# tictactoe.net
KiCad netlist of a schematic drawn in EAGLE
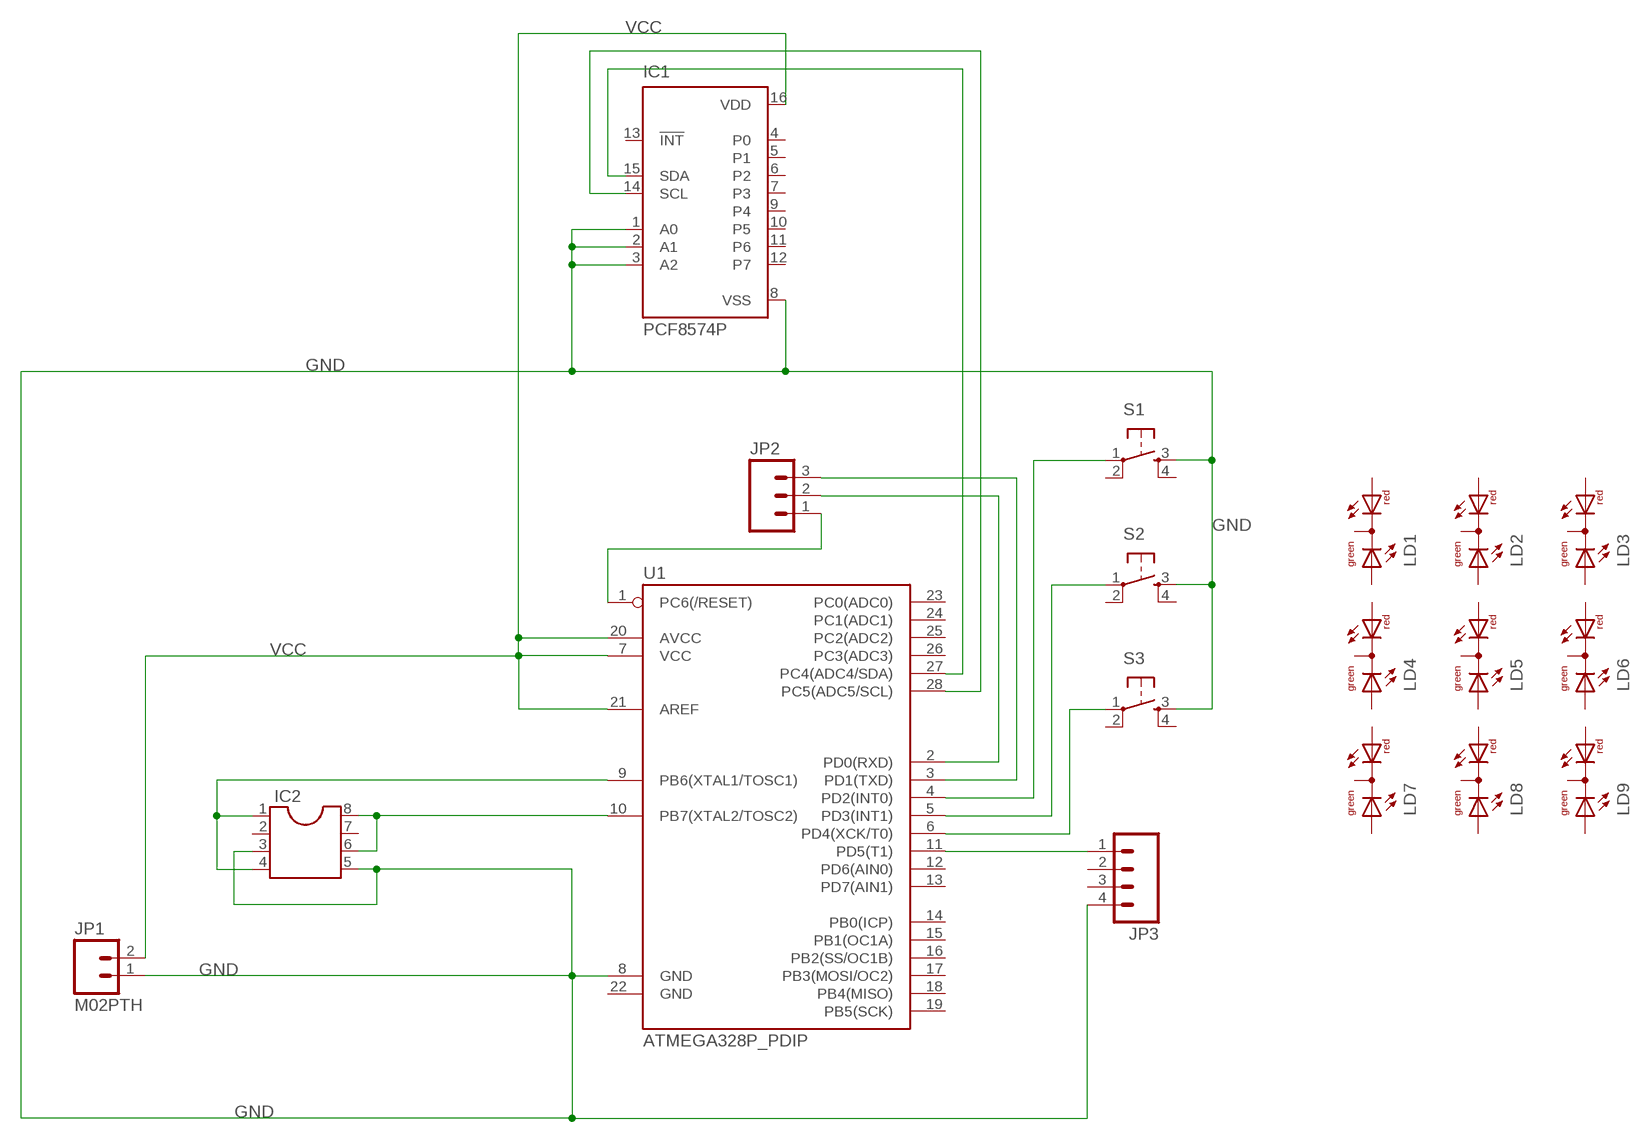
[diagram p0: schematic, sheet 1]

(export (version "E")
  (design (tool "Eeschema 10.0.6"))
  (components
    (comp (ref "IC1")
      (value "PCF8574P")
      (footprint "eagle-import:DIL16")
      (fields (field (name "MPN") "PCF8574PN"))
      (libsource (lib "eagle-import") (part "PCF8574P"))
    )
    (comp (ref "IC2")
      (value "DIL8S")
      (footprint "eagle-import:SOCKET-08")
      (libsource (lib "eagle-import") (part "DIL8S"))
    )
    (comp (ref "JP1")
      (value "M02PTH")
      (footprint "eagle-import:1X02")
      (libsource (lib "eagle-import") (part "M02PTH"))
    )
    (comp (ref "JP2")
      (value "M03PTH")
      (footprint "eagle-import:1X03")
      (libsource (lib "eagle-import") (part "M03PTH"))
    )
    (comp (ref "JP3")
      (value "M04PTH")
      (footprint "eagle-import:1X04")
      (libsource (lib "eagle-import") (part "M04PTH"))
    )
    (comp (ref "LD1")
      (value "DUOLED-RG-C")
      (footprint "eagle-import:DUOLED-C-5MM")
      (libsource (lib "eagle-import") (part "DUOLED-RG-C"))
    )
    (comp (ref "LD2")
      (value "DUOLED-RG-C")
      (footprint "eagle-import:DUOLED-C-5MM")
      (libsource (lib "eagle-import") (part "DUOLED-RG-C"))
    )
    (comp (ref "LD3")
      (value "DUOLED-RG-C")
      (footprint "eagle-import:DUOLED-C-5MM")
      (libsource (lib "eagle-import") (part "DUOLED-RG-C"))
    )
    (comp (ref "LD4")
      (value "DUOLED-RG-C")
      (footprint "eagle-import:DUOLED-C-5MM")
      (libsource (lib "eagle-import") (part "DUOLED-RG-C"))
    )
    (comp (ref "LD5")
      (value "DUOLED-RG-C")
      (footprint "eagle-import:DUOLED-C-5MM")
      (libsource (lib "eagle-import") (part "DUOLED-RG-C"))
    )
    (comp (ref "LD6")
      (value "DUOLED-RG-C")
      (footprint "eagle-import:DUOLED-C-5MM")
      (libsource (lib "eagle-import") (part "DUOLED-RG-C"))
    )
    (comp (ref "LD7")
      (value "DUOLED-RG-C")
      (footprint "eagle-import:DUOLED-C-5MM")
      (libsource (lib "eagle-import") (part "DUOLED-RG-C"))
    )
    (comp (ref "LD8")
      (value "DUOLED-RG-C")
      (footprint "eagle-import:DUOLED-C-5MM")
      (libsource (lib "eagle-import") (part "DUOLED-RG-C"))
    )
    (comp (ref "LD9")
      (value "DUOLED-RG-C")
      (footprint "eagle-import:DUOLED-C-5MM")
      (libsource (lib "eagle-import") (part "DUOLED-RG-C"))
    )
    (comp (ref "S1")
      (value "TAC_SWITCHPTH")
      (footprint "eagle-import:TACTILE-PTH")
      (libsource (lib "eagle-import") (part "TAC_SWITCHPTH"))
    )
    (comp (ref "S2")
      (value "TAC_SWITCHPTH")
      (footprint "eagle-import:TACTILE-PTH")
      (libsource (lib "eagle-import") (part "TAC_SWITCHPTH"))
    )
    (comp (ref "S3")
      (value "TAC_SWITCHPTH")
      (footprint "eagle-import:TACTILE-PTH")
      (libsource (lib "eagle-import") (part "TAC_SWITCHPTH"))
    )
    (comp (ref "U1")
      (value "ATMEGA328P_PDIP")
      (footprint "eagle-import:DIL28-3")
      (libsource (lib "eagle-import") (part "ATMEGA328P_PDIP"))
    )
  )
  (nets
    (net (code "1") (name "/GND") (class "Default")
      (node (ref "IC1") (pin "1") (pinfunction "A0_1") (pintype "input"))
      (node (ref "IC1") (pin "2") (pinfunction "A1_2") (pintype "input"))
      (node (ref "IC1") (pin "3") (pinfunction "A2_3") (pintype "input"))
      (node (ref "IC1") (pin "8") (pinfunction "VSS_8") (pintype "power_in"))
      (node (ref "IC2") (pin "3") (pinfunction "3_3") (pintype "passive"))
      (node (ref "IC2") (pin "5") (pinfunction "5_5") (pintype "passive"))
      (node (ref "JP1") (pin "1") (pinfunction "1_1") (pintype "passive"))
      (node (ref "JP3") (pin "4") (pinfunction "4_4") (pintype "passive"))
      (node (ref "S1") (pin "3") (pinfunction "3_3") (pintype "passive"))
      (node (ref "S2") (pin "3") (pinfunction "3_3") (pintype "passive"))
      (node (ref "S3") (pin "3") (pinfunction "3_3") (pintype "passive"))
      (node (ref "U1") (pin "8") (pinfunction "GND_8") (pintype "bidirectional"))
    )
    (net (code "2") (name "/VCC") (class "Default")
      (node (ref "IC1") (pin "16") (pinfunction "VDD_16") (pintype "power_in"))
      (node (ref "JP1") (pin "2") (pinfunction "2_2") (pintype "passive"))
      (node (ref "U1") (pin "20") (pinfunction "AVCC_20") (pintype "bidirectional"))
      (node (ref "U1") (pin "21") (pinfunction "AREF_21") (pintype "bidirectional"))
      (node (ref "U1") (pin "7") (pinfunction "VCC_7") (pintype "bidirectional"))
    )
    (net (code "3") (name "Net-(IC1-SCL)") (class "Default")
      (node (ref "IC1") (pin "14") (pinfunction "SCL_14") (pintype "input"))
      (node (ref "U1") (pin "28") (pinfunction "PC5(ADC5/SCL)_28") (pintype "bidirectional"))
    )
    (net (code "4") (name "Net-(IC1-SDA)") (class "Default")
      (node (ref "IC1") (pin "15") (pinfunction "SDA_15") (pintype "bidirectional"))
      (node (ref "U1") (pin "27") (pinfunction "PC4(ADC4/SDA)_27") (pintype "bidirectional"))
    )
    (net (code "5") (name "Net-(U1-PB6(XTAL1{slash}TOSC1))") (class "Default")
      (node (ref "IC2") (pin "1") (pinfunction "1_1") (pintype "passive"))
      (node (ref "IC2") (pin "4") (pinfunction "4_4") (pintype "passive"))
      (node (ref "U1") (pin "9") (pinfunction "PB6(XTAL1/TOSC1)_9") (pintype "bidirectional"))
    )
    (net (code "6") (name "Net-(U1-PB7(XTAL2{slash}TOSC2))") (class "Default")
      (node (ref "IC2") (pin "6") (pinfunction "6_6") (pintype "passive"))
      (node (ref "IC2") (pin "8") (pinfunction "8_8") (pintype "passive"))
      (node (ref "U1") (pin "10") (pinfunction "PB7(XTAL2/TOSC2)_10") (pintype "bidirectional"))
    )
    (net (code "7") (name "Net-(U1-PC6({slash}RESET))") (class "Default")
      (node (ref "JP2") (pin "1") (pinfunction "1_1") (pintype "passive"))
      (node (ref "U1") (pin "1") (pinfunction "PC6(/RESET)_1") (pintype "bidirectional"))
    )
    (net (code "8") (name "Net-(U1-PD0(RXD))") (class "Default")
      (node (ref "JP2") (pin "2") (pinfunction "2_2") (pintype "passive"))
      (node (ref "U1") (pin "2") (pinfunction "PD0(RXD)_2") (pintype "bidirectional"))
    )
    (net (code "9") (name "Net-(U1-PD1(TXD))") (class "Default")
      (node (ref "JP2") (pin "3") (pinfunction "3_3") (pintype "passive"))
      (node (ref "U1") (pin "3") (pinfunction "PD1(TXD)_3") (pintype "bidirectional"))
    )
    (net (code "10") (name "Net-(U1-PD2(INT0))") (class "Default")
      (node (ref "S1") (pin "1") (pinfunction "1_1") (pintype "passive"))
      (node (ref "U1") (pin "4") (pinfunction "PD2(INT0)_4") (pintype "bidirectional"))
    )
    (net (code "11") (name "Net-(U1-PD3(INT1))") (class "Default")
      (node (ref "S2") (pin "1") (pinfunction "1_1") (pintype "passive"))
      (node (ref "U1") (pin "5") (pinfunction "PD3(INT1)_5") (pintype "bidirectional"))
    )
    (net (code "12") (name "Net-(U1-PD4(XCK{slash}T0))") (class "Default")
      (node (ref "S3") (pin "1") (pinfunction "1_1") (pintype "passive"))
      (node (ref "U1") (pin "6") (pinfunction "PD4(XCK/T0)_6") (pintype "bidirectional"))
    )
    (net (code "13") (name "Net-(U1-PD5(T1))") (class "Default")
      (node (ref "JP3") (pin "1") (pinfunction "1_1") (pintype "passive"))
      (node (ref "U1") (pin "11") (pinfunction "PD5(T1)_11") (pintype "bidirectional"))
    )
    (net (code "14") (name "unconnected-(IC1-P0-Pad4)") (class "Default")
      (node (ref "IC1") (pin "4") (pinfunction "P0_4") (pintype "bidirectional"))
    )
    (net (code "15") (name "unconnected-(IC1-P1-Pad5)") (class "Default")
      (node (ref "IC1") (pin "5") (pinfunction "P1_5") (pintype "bidirectional"))
    )
    (net (code "16") (name "unconnected-(IC1-P2-Pad6)") (class "Default")
      (node (ref "IC1") (pin "6") (pinfunction "P2_6") (pintype "bidirectional"))
    )
    (net (code "17") (name "unconnected-(IC1-P3-Pad7)") (class "Default")
      (node (ref "IC1") (pin "7") (pinfunction "P3_7") (pintype "bidirectional"))
    )
    (net (code "18") (name "unconnected-(IC1-P4-Pad9)") (class "Default")
      (node (ref "IC1") (pin "9") (pinfunction "P4_9") (pintype "bidirectional"))
    )
    (net (code "19") (name "unconnected-(IC1-P5-Pad10)") (class "Default")
      (node (ref "IC1") (pin "10") (pinfunction "P5_10") (pintype "bidirectional"))
    )
    (net (code "20") (name "unconnected-(IC1-P6-Pad11)") (class "Default")
      (node (ref "IC1") (pin "11") (pinfunction "P6_11") (pintype "bidirectional"))
    )
    (net (code "21") (name "unconnected-(IC1-P7-Pad12)") (class "Default")
      (node (ref "IC1") (pin "12") (pinfunction "P7_12") (pintype "bidirectional"))
    )
    (net (code "22") (name "unconnected-(IC1-~{INT}-Pad13)") (class "Default")
      (node (ref "IC1") (pin "13") (pinfunction "~{INT}_13") (pintype "output"))
    )
    (net (code "23") (name "unconnected-(IC2-Pad2)") (class "Default")
      (node (ref "IC2") (pin "2") (pinfunction "2_2") (pintype "passive"))
    )
    (net (code "24") (name "unconnected-(IC2-Pad7)") (class "Default")
      (node (ref "IC2") (pin "7") (pinfunction "7_7") (pintype "passive"))
    )
    (net (code "25") (name "unconnected-(JP3-Pad2)") (class "Default")
      (node (ref "JP3") (pin "2") (pinfunction "2_2") (pintype "passive"))
    )
    (net (code "26") (name "unconnected-(JP3-Pad3)") (class "Default")
      (node (ref "JP3") (pin "3") (pinfunction "3_3") (pintype "passive"))
    )
    (net (code "27") (name "unconnected-(LD1-AG-PadAX)") (class "Default")
      (node (ref "LD1") (pin "AX") (pinfunction "AG_AX") (pintype "passive"))
    )
    (net (code "28") (name "unconnected-(LD1-PadAR)") (class "Default")
      (node (ref "LD1") (pin "AR") (pinfunction "AR_AR") (pintype "passive"))
    )
    (net (code "29") (name "unconnected-(LD1-PadC)") (class "Default")
      (node (ref "LD1") (pin "C") (pinfunction "C_C") (pintype "passive"))
    )
    (net (code "30") (name "unconnected-(LD2-AG-PadAX)") (class "Default")
      (node (ref "LD2") (pin "AX") (pinfunction "AG_AX") (pintype "passive"))
    )
    (net (code "31") (name "unconnected-(LD2-PadAR)") (class "Default")
      (node (ref "LD2") (pin "AR") (pinfunction "AR_AR") (pintype "passive"))
    )
    (net (code "32") (name "unconnected-(LD2-PadC)") (class "Default")
      (node (ref "LD2") (pin "C") (pinfunction "C_C") (pintype "passive"))
    )
    (net (code "33") (name "unconnected-(LD3-AG-PadAX)") (class "Default")
      (node (ref "LD3") (pin "AX") (pinfunction "AG_AX") (pintype "passive"))
    )
    (net (code "34") (name "unconnected-(LD3-PadAR)") (class "Default")
      (node (ref "LD3") (pin "AR") (pinfunction "AR_AR") (pintype "passive"))
    )
    (net (code "35") (name "unconnected-(LD3-PadC)") (class "Default")
      (node (ref "LD3") (pin "C") (pinfunction "C_C") (pintype "passive"))
    )
    (net (code "36") (name "unconnected-(LD4-AG-PadAX)") (class "Default")
      (node (ref "LD4") (pin "AX") (pinfunction "AG_AX") (pintype "passive"))
    )
    (net (code "37") (name "unconnected-(LD4-PadAR)") (class "Default")
      (node (ref "LD4") (pin "AR") (pinfunction "AR_AR") (pintype "passive"))
    )
    (net (code "38") (name "unconnected-(LD4-PadC)") (class "Default")
      (node (ref "LD4") (pin "C") (pinfunction "C_C") (pintype "passive"))
    )
    (net (code "39") (name "unconnected-(LD5-AG-PadAX)") (class "Default")
      (node (ref "LD5") (pin "AX") (pinfunction "AG_AX") (pintype "passive"))
    )
    (net (code "40") (name "unconnected-(LD5-PadAR)") (class "Default")
      (node (ref "LD5") (pin "AR") (pinfunction "AR_AR") (pintype "passive"))
    )
    (net (code "41") (name "unconnected-(LD5-PadC)") (class "Default")
      (node (ref "LD5") (pin "C") (pinfunction "C_C") (pintype "passive"))
    )
    (net (code "42") (name "unconnected-(LD6-AG-PadAX)") (class "Default")
      (node (ref "LD6") (pin "AX") (pinfunction "AG_AX") (pintype "passive"))
    )
    (net (code "43") (name "unconnected-(LD6-PadAR)") (class "Default")
      (node (ref "LD6") (pin "AR") (pinfunction "AR_AR") (pintype "passive"))
    )
    (net (code "44") (name "unconnected-(LD6-PadC)") (class "Default")
      (node (ref "LD6") (pin "C") (pinfunction "C_C") (pintype "passive"))
    )
    (net (code "45") (name "unconnected-(LD7-AG-PadAX)") (class "Default")
      (node (ref "LD7") (pin "AX") (pinfunction "AG_AX") (pintype "passive"))
    )
    (net (code "46") (name "unconnected-(LD7-PadAR)") (class "Default")
      (node (ref "LD7") (pin "AR") (pinfunction "AR_AR") (pintype "passive"))
    )
    (net (code "47") (name "unconnected-(LD7-PadC)") (class "Default")
      (node (ref "LD7") (pin "C") (pinfunction "C_C") (pintype "passive"))
    )
    (net (code "48") (name "unconnected-(LD8-AG-PadAX)") (class "Default")
      (node (ref "LD8") (pin "AX") (pinfunction "AG_AX") (pintype "passive"))
    )
    (net (code "49") (name "unconnected-(LD8-PadAR)") (class "Default")
      (node (ref "LD8") (pin "AR") (pinfunction "AR_AR") (pintype "passive"))
    )
    (net (code "50") (name "unconnected-(LD8-PadC)") (class "Default")
      (node (ref "LD8") (pin "C") (pinfunction "C_C") (pintype "passive"))
    )
    (net (code "51") (name "unconnected-(LD9-AG-PadAX)") (class "Default")
      (node (ref "LD9") (pin "AX") (pinfunction "AG_AX") (pintype "passive"))
    )
    (net (code "52") (name "unconnected-(LD9-PadAR)") (class "Default")
      (node (ref "LD9") (pin "AR") (pinfunction "AR_AR") (pintype "passive"))
    )
    (net (code "53") (name "unconnected-(LD9-PadC)") (class "Default")
      (node (ref "LD9") (pin "C") (pinfunction "C_C") (pintype "passive"))
    )
    (net (code "54") (name "unconnected-(S1-Pad2)") (class "Default")
      (node (ref "S1") (pin "2") (pinfunction "2_2") (pintype "passive"))
    )
    (net (code "55") (name "unconnected-(S1-Pad4)") (class "Default")
      (node (ref "S1") (pin "4") (pinfunction "4_4") (pintype "passive"))
    )
    (net (code "56") (name "unconnected-(S2-Pad2)") (class "Default")
      (node (ref "S2") (pin "2") (pinfunction "2_2") (pintype "passive"))
    )
    (net (code "57") (name "unconnected-(S2-Pad4)") (class "Default")
      (node (ref "S2") (pin "4") (pinfunction "4_4") (pintype "passive"))
    )
    (net (code "58") (name "unconnected-(S3-Pad2)") (class "Default")
      (node (ref "S3") (pin "2") (pinfunction "2_2") (pintype "passive"))
    )
    (net (code "59") (name "unconnected-(S3-Pad4)") (class "Default")
      (node (ref "S3") (pin "4") (pinfunction "4_4") (pintype "passive"))
    )
    (net (code "60") (name "unconnected-(U1-GND-Pad22)") (class "Default")
      (node (ref "U1") (pin "22") (pinfunction "GND_22") (pintype "bidirectional"))
    )
    (net (code "61") (name "unconnected-(U1-PB0(ICP)-Pad14)") (class "Default")
      (node (ref "U1") (pin "14") (pinfunction "PB0(ICP)_14") (pintype "bidirectional"))
    )
    (net (code "62") (name "unconnected-(U1-PB1(OC1A)-Pad15)") (class "Default")
      (node (ref "U1") (pin "15") (pinfunction "PB1(OC1A)_15") (pintype "bidirectional"))
    )
    (net (code "63") (name "unconnected-(U1-PB2(SS{slash}OC1B)-Pad16)") (class "Default")
      (node (ref "U1") (pin "16") (pinfunction "PB2(SS/OC1B)_16") (pintype "bidirectional"))
    )
    (net (code "64") (name "unconnected-(U1-PB3(MOSI{slash}OC2)-Pad17)") (class "Default")
      (node (ref "U1") (pin "17") (pinfunction "PB3(MOSI/OC2)_17") (pintype "bidirectional"))
    )
    (net (code "65") (name "unconnected-(U1-PB4(MISO)-Pad18)") (class "Default")
      (node (ref "U1") (pin "18") (pinfunction "PB4(MISO)_18") (pintype "bidirectional"))
    )
    (net (code "66") (name "unconnected-(U1-PB5(SCK)-Pad19)") (class "Default")
      (node (ref "U1") (pin "19") (pinfunction "PB5(SCK)_19") (pintype "bidirectional"))
    )
    (net (code "67") (name "unconnected-(U1-PC0(ADC0)-Pad23)") (class "Default")
      (node (ref "U1") (pin "23") (pinfunction "PC0(ADC0)_23") (pintype "bidirectional"))
    )
    (net (code "68") (name "unconnected-(U1-PC1(ADC1)-Pad24)") (class "Default")
      (node (ref "U1") (pin "24") (pinfunction "PC1(ADC1)_24") (pintype "bidirectional"))
    )
    (net (code "69") (name "unconnected-(U1-PC2(ADC2)-Pad25)") (class "Default")
      (node (ref "U1") (pin "25") (pinfunction "PC2(ADC2)_25") (pintype "bidirectional"))
    )
    (net (code "70") (name "unconnected-(U1-PC3(ADC3)-Pad26)") (class "Default")
      (node (ref "U1") (pin "26") (pinfunction "PC3(ADC3)_26") (pintype "bidirectional"))
    )
    (net (code "71") (name "unconnected-(U1-PD6(AIN0)-Pad12)") (class "Default")
      (node (ref "U1") (pin "12") (pinfunction "PD6(AIN0)_12") (pintype "bidirectional"))
    )
    (net (code "72") (name "unconnected-(U1-PD7(AIN1)-Pad13)") (class "Default")
      (node (ref "U1") (pin "13") (pinfunction "PD7(AIN1)_13") (pintype "bidirectional"))
    )
  )
)
